# Clock_with_LED.net
KiCad netlist of a schematic drawn in EAGLE
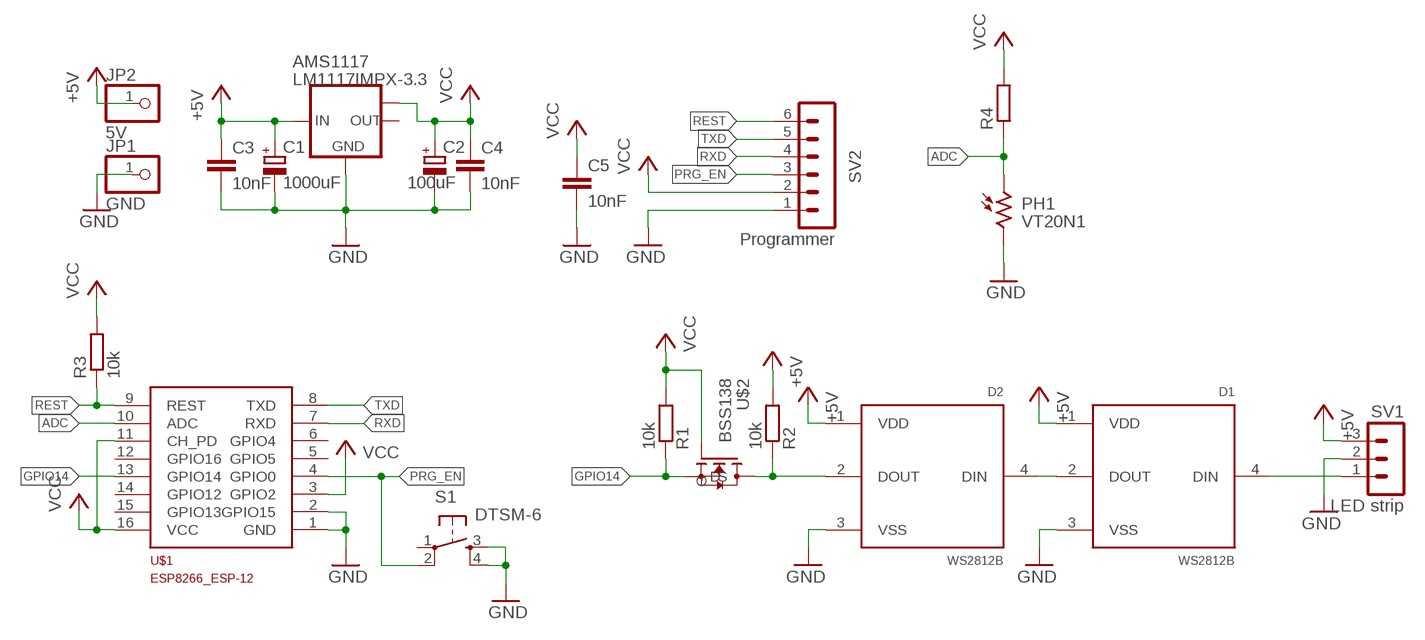
[diagram p0: schematic, sheet 1]

(export (version "E")
  (design (tool "Eeschema 10.0.6"))
  (components
    (comp (ref "AMS1117")
      (value "LM1117IMPX-3.3")
      (footprint "eagle-import:SOT223")
      (libsource (lib "eagle-import") (part "LM1117IMPX-3.3"))
    )
    (comp (ref "C1")
      (value "1000uF")
      (footprint "eagle-import:TT5D11L")
      (libsource (lib "eagle-import") (part "CPOL-EUTT5D11L"))
    )
    (comp (ref "C2")
      (value "100uF")
      (footprint "eagle-import:TT5D7L")
      (libsource (lib "eagle-import") (part "CPOL-EUTT5D7L"))
    )
    (comp (ref "C3")
      (value "10nF")
      (footprint "eagle-import:C0805")
      (libsource (lib "eagle-import") (part "C-EUC0805"))
    )
    (comp (ref "C4")
      (value "10nF")
      (footprint "eagle-import:C0805")
      (libsource (lib "eagle-import") (part "C-EUC0805"))
    )
    (comp (ref "C5")
      (value "10nF")
      (footprint "eagle-import:C0805")
      (libsource (lib "eagle-import") (part "C-EUC0805"))
    )
    (comp (ref "D1")
      (value "WS2812B")
      (footprint "eagle-import:LED_WS2812B")
      (fields (field (name "MF") "Adafruit Industries"))
      (libsource (lib "eagle-import") (part "WS2812B"))
    )
    (comp (ref "D2")
      (value "WS2812B")
      (footprint "eagle-import:LED_WS2812B")
      (fields (field (name "MF") "Adafruit Industries"))
      (libsource (lib "eagle-import") (part "WS2812B"))
    )
    (comp (ref "JP1")
      (value "GND")
      (footprint "eagle-import:1X01")
      (libsource (lib "eagle-import") (part "PINHD-1X1"))
    )
    (comp (ref "JP2")
      (value "5V")
      (footprint "eagle-import:1X01")
      (libsource (lib "eagle-import") (part "PINHD-1X1"))
    )
    (comp (ref "PH1")
      (value "VT20N1")
      (footprint "eagle-import:TO46-VT200")
      (libsource (lib "eagle-import") (part "VT20N1"))
    )
    (comp (ref "R1")
      (value "10k")
      (footprint "eagle-import:R0805")
      (libsource (lib "eagle-import") (part "R-EU_R0805"))
    )
    (comp (ref "R2")
      (value "10k")
      (footprint "eagle-import:R0805")
      (libsource (lib "eagle-import") (part "R-EU_R0805"))
    )
    (comp (ref "R3")
      (value "10k")
      (footprint "eagle-import:R0805")
      (libsource (lib "eagle-import") (part "R-EU_R0805"))
    )
    (comp (ref "R4")
      (value "R-EU_R0805")
      (footprint "eagle-import:R0805")
      (libsource (lib "eagle-import") (part "R-EU_R0805"))
    )
    (comp (ref "S1")
      (value "DTSM-6")
      (footprint "eagle-import:DTSM-6")
      (libsource (lib "eagle-import") (part "DTSM-6"))
    )
    (comp (ref "SV1")
      (value "LED strip")
      (footprint "eagle-import:MA03-1")
      (libsource (lib "eagle-import") (part "MA03-1"))
    )
    (comp (ref "SV2")
      (value "Programmer")
      (footprint "eagle-import:MA06-1")
      (libsource (lib "eagle-import") (part "MA06-1"))
    )
    (comp (ref "U$1")
      (value "ESP8266_ESP-12")
      (footprint "eagle-import:ESP8266-ESP12")
      (libsource (lib "eagle-import") (part "ESP8266_ESP-12"))
    )
    (comp (ref "U$2")
      (value "BSS138")
      (footprint "eagle-import:BSS138")
      (fields (field (name "MF") "Fairchild Semiconductor"))
      (libsource (lib "eagle-import") (part "BSS138"))
    )
  )
  (nets
    (net (code "1") (name "+5V") (class "Default")
      (node (ref "AMS1117") (pin "3") (pinfunction "IN_3") (pintype "input"))
      (node (ref "C1") (pin "+") (pinfunction "+_+") (pintype "passive"))
      (node (ref "C3") (pin "1") (pinfunction "1_1") (pintype "passive"))
      (node (ref "D1") (pin "1") (pinfunction "VDD_1") (pintype "power_in"))
      (node (ref "D2") (pin "1") (pinfunction "VDD_1") (pintype "power_in"))
      (node (ref "JP2") (pin "1") (pinfunction "1_1") (pintype "passive"))
      (node (ref "R2") (pin "2") (pinfunction "2_2") (pintype "passive"))
      (node (ref "SV1") (pin "3") (pinfunction "3_3") (pintype "passive"))
    )
    (net (code "2") (name "ADC") (class "Default")
      (node (ref "PH1") (pin "1") (pinfunction "1_1") (pintype "passive"))
      (node (ref "R4") (pin "1") (pinfunction "1_1") (pintype "passive"))
      (node (ref "U$1") (pin "10") (pinfunction "ADC_10") (pintype "bidirectional"))
    )
    (net (code "3") (name "GND") (class "Default")
      (node (ref "AMS1117") (pin "1") (pinfunction "GND_1") (pintype "input"))
      (node (ref "C1") (pin "-") (pinfunction "-_-") (pintype "passive"))
      (node (ref "C2") (pin "-") (pinfunction "-_-") (pintype "passive"))
      (node (ref "C3") (pin "2") (pinfunction "2_2") (pintype "passive"))
      (node (ref "C4") (pin "2") (pinfunction "2_2") (pintype "passive"))
      (node (ref "C5") (pin "2") (pinfunction "2_2") (pintype "passive"))
      (node (ref "D1") (pin "3") (pinfunction "VSS_3") (pintype "passive"))
      (node (ref "D2") (pin "3") (pinfunction "VSS_3") (pintype "passive"))
      (node (ref "JP1") (pin "1") (pinfunction "1_1") (pintype "passive"))
      (node (ref "PH1") (pin "2") (pinfunction "2_2") (pintype "passive"))
      (node (ref "S1") (pin "3") (pinfunction "3_3") (pintype "passive"))
      (node (ref "S1") (pin "4") (pinfunction "4_4") (pintype "passive"))
      (node (ref "SV1") (pin "2") (pinfunction "2_2") (pintype "passive"))
      (node (ref "SV2") (pin "1") (pinfunction "1_1") (pintype "passive"))
      (node (ref "U$1") (pin "1") (pinfunction "GND_1") (pintype "bidirectional"))
      (node (ref "U$1") (pin "2") (pinfunction "GPIO15_2") (pintype "bidirectional"))
    )
    (net (code "4") (name "GPIO14") (class "Default")
      (node (ref "R1") (pin "1") (pinfunction "1_1") (pintype "passive"))
      (node (ref "U$1") (pin "13") (pinfunction "GPIO14_13") (pintype "bidirectional"))
      (node (ref "U$2") (pin "S") (pinfunction "S_S") (pintype "passive"))
    )
    (net (code "5") (name "Net-(D1-DIN)") (class "Default")
      (node (ref "D1") (pin "4") (pinfunction "DIN_4") (pintype "input"))
      (node (ref "SV1") (pin "1") (pinfunction "1_1") (pintype "passive"))
    )
    (net (code "6") (name "Net-(D1-DOUT)") (class "Default")
      (node (ref "D1") (pin "2") (pinfunction "DOUT_2") (pintype "output"))
      (node (ref "D2") (pin "4") (pinfunction "DIN_4") (pintype "input"))
    )
    (net (code "7") (name "Net-(D2-DOUT)") (class "Default")
      (node (ref "D2") (pin "2") (pinfunction "DOUT_2") (pintype "output"))
      (node (ref "R2") (pin "1") (pinfunction "1_1") (pintype "passive"))
      (node (ref "U$2") (pin "D") (pinfunction "D_D") (pintype "passive"))
    )
    (net (code "8") (name "PRG_EN") (class "Default")
      (node (ref "S1") (pin "2") (pinfunction "2_2") (pintype "passive"))
      (node (ref "SV2") (pin "3") (pinfunction "3_3") (pintype "passive"))
      (node (ref "U$1") (pin "4") (pinfunction "GPIO0_4") (pintype "bidirectional"))
    )
    (net (code "9") (name "REST") (class "Default")
      (node (ref "R3") (pin "1") (pinfunction "1_1") (pintype "passive"))
      (node (ref "SV2") (pin "6") (pinfunction "6_6") (pintype "passive"))
      (node (ref "U$1") (pin "9") (pinfunction "REST_9") (pintype "bidirectional"))
    )
    (net (code "10") (name "RXD") (class "Default")
      (node (ref "SV2") (pin "4") (pinfunction "4_4") (pintype "passive"))
      (node (ref "U$1") (pin "7") (pinfunction "RXD_7") (pintype "bidirectional"))
    )
    (net (code "11") (name "TXD") (class "Default")
      (node (ref "SV2") (pin "5") (pinfunction "5_5") (pintype "passive"))
      (node (ref "U$1") (pin "8") (pinfunction "TXD_8") (pintype "bidirectional"))
    )
    (net (code "12") (name "VCC") (class "Default")
      (node (ref "AMS1117") (pin "TAB") (pinfunction "OUT1_TAB") (pintype "passive"))
      (node (ref "C2") (pin "+") (pinfunction "+_+") (pintype "passive"))
      (node (ref "C4") (pin "1") (pinfunction "1_1") (pintype "passive"))
      (node (ref "C5") (pin "1") (pinfunction "1_1") (pintype "passive"))
      (node (ref "R1") (pin "2") (pinfunction "2_2") (pintype "passive"))
      (node (ref "R3") (pin "2") (pinfunction "2_2") (pintype "passive"))
      (node (ref "R4") (pin "2") (pinfunction "2_2") (pintype "passive"))
      (node (ref "SV2") (pin "2") (pinfunction "2_2") (pintype "passive"))
      (node (ref "U$1") (pin "11") (pinfunction "CH_PD_11") (pintype "bidirectional"))
      (node (ref "U$1") (pin "16") (pinfunction "VCC_16") (pintype "bidirectional"))
      (node (ref "U$1") (pin "3") (pinfunction "GPIO2_3") (pintype "bidirectional"))
      (node (ref "U$2") (pin "G") (pinfunction "G_G") (pintype "passive"))
    )
    (net (code "13") (name "unconnected-(AMS1117-OUT-Pad2)") (class "Default")
      (node (ref "AMS1117") (pin "2") (pinfunction "OUT_2") (pintype "passive"))
    )
    (net (code "14") (name "unconnected-(S1-Pad1)") (class "Default")
      (node (ref "S1") (pin "1") (pinfunction "1_1") (pintype "passive"))
    )
    (net (code "15") (name "unconnected-(U$1-GPIO4-Pad6)") (class "Default")
      (node (ref "U$1") (pin "6") (pinfunction "GPIO4_6") (pintype "bidirectional"))
    )
    (net (code "16") (name "unconnected-(U$1-GPIO5-Pad5)") (class "Default")
      (node (ref "U$1") (pin "5") (pinfunction "GPIO5_5") (pintype "bidirectional"))
    )
    (net (code "17") (name "unconnected-(U$1-GPIO12-Pad14)") (class "Default")
      (node (ref "U$1") (pin "14") (pinfunction "GPIO12_14") (pintype "bidirectional"))
    )
    (net (code "18") (name "unconnected-(U$1-GPIO13-Pad15)") (class "Default")
      (node (ref "U$1") (pin "15") (pinfunction "GPIO13_15") (pintype "bidirectional"))
    )
    (net (code "19") (name "unconnected-(U$1-GPIO16-Pad12)") (class "Default")
      (node (ref "U$1") (pin "12") (pinfunction "GPIO16_12") (pintype "bidirectional"))
    )
  )
)
